# Ethernet.net
KiCad netlist of a schematic drawn in Altium Designer
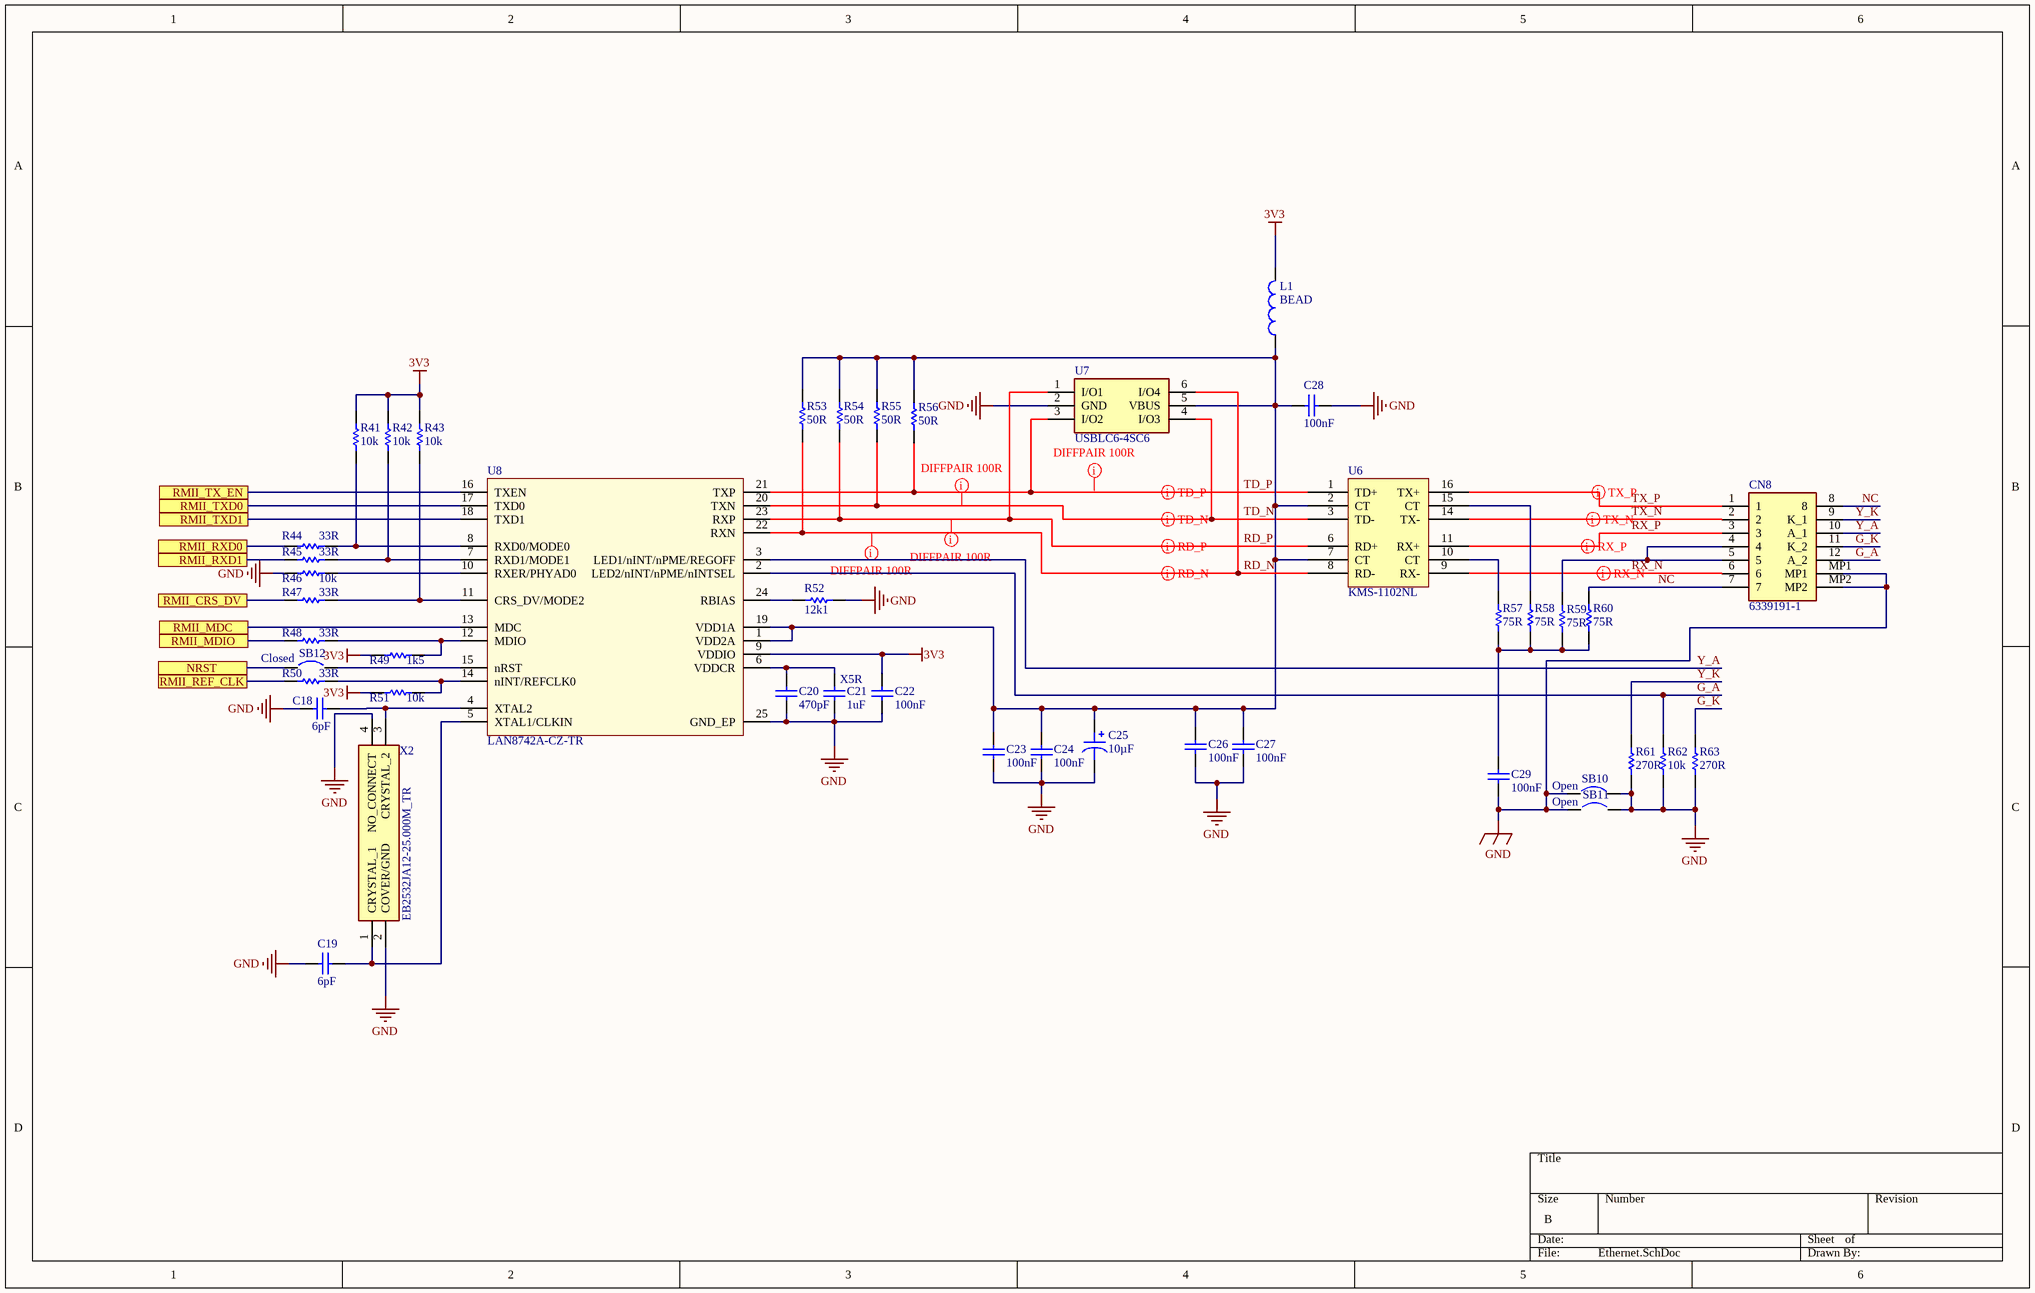
[diagram p0: Ethernet.SchDoc]

(export (version "E")
  (design (tool "Eeschema 10.0.6"))
  (components
    (comp (ref "C18")
      (value "6pF")
      (footprint "1608[0603]")
      (description "Capacitor")
      (fields (field (name "Comment") "Cap") (field (name "PUBLISHER") "Altium Limited"))
      (libsource (lib "Miscellaneous Devices") (part "Cap"))
    )
    (comp (ref "C19")
      (value "6pF")
      (footprint "1608[0603]")
      (description "Capacitor")
      (fields (field (name "Comment") "Cap") (field (name "PUBLISHER") "Altium Limited"))
      (libsource (lib "Miscellaneous Devices") (part "Cap"))
    )
    (comp (ref "C20")
      (value "470pF")
      (footprint "1608[0603]")
      (description "Capacitor")
      (fields (field (name "Comment") "Cap") (field (name "PUBLISHER") "Altium Limited"))
      (libsource (lib "Miscellaneous Devices") (part "Cap"))
    )
    (comp (ref "C21")
      (value "X5R")
      (footprint "1608[0603]")
      (description "Capacitor")
      (fields (field (name "ALTIUM_VALUE") "1uF") (field (name "PUBLISHER") "Altium Limited"))
      (libsource (lib "Miscellaneous Devices") (part "Cap"))
    )
    (comp (ref "C22")
      (value "100nF")
      (footprint "1608[0603]")
      (description "Capacitor")
      (fields (field (name "Comment") "Cap") (field (name "PUBLISHER") "Altium Limited"))
      (libsource (lib "Miscellaneous Devices") (part "Cap"))
    )
    (comp (ref "C23")
      (value "100nF")
      (footprint "1608[0603]")
      (description "Capacitor")
      (fields (field (name "Comment") "Cap") (field (name "PUBLISHER") "Altium Limited"))
      (libsource (lib "Miscellaneous Devices") (part "Cap"))
    )
    (comp (ref "C24")
      (value "100nF")
      (footprint "1608[0603]")
      (description "Capacitor")
      (fields (field (name "Comment") "Cap") (field (name "PUBLISHER") "Altium Limited"))
      (libsource (lib "Miscellaneous Devices") (part "Cap"))
    )
    (comp (ref "C25")
      (value "10µF")
      (footprint "CAP ALSMD 5.3MM H5.4MM")
      (description "CAP ALUM 10UF 20% 16V SMD")
      (fields (field (name "PART NUMBER") "UZP1C100MCL1GB") (field (name "MANUFACTURER") "Nichicon"))
      (libsource (lib "Celestial Altium Library - altium_library") (part "Polarised Capacitor"))
    )
    (comp (ref "C26")
      (value "100nF")
      (footprint "1608[0603]")
      (description "Capacitor")
      (fields (field (name "Comment") "Cap") (field (name "PUBLISHER") "Altium Limited"))
      (libsource (lib "Miscellaneous Devices") (part "Cap"))
    )
    (comp (ref "C27")
      (value "100nF")
      (footprint "1608[0603]")
      (description "Capacitor")
      (fields (field (name "Comment") "Cap") (field (name "PUBLISHER") "Altium Limited"))
      (libsource (lib "Miscellaneous Devices") (part "Cap"))
    )
    (comp (ref "C28")
      (value "100nF")
      (footprint "1608[0603]")
      (description "Capacitor")
      (fields (field (name "Comment") "Cap") (field (name "PUBLISHER") "Altium Limited"))
      (libsource (lib "Miscellaneous Devices") (part "Cap"))
    )
    (comp (ref "C29")
      (value "100nF")
      (footprint "1608[0603]")
      (description "Capacitor")
      (fields (field (name "Comment") "Cap") (field (name "PUBLISHER") "Altium Limited"))
      (libsource (lib "Miscellaneous Devices") (part "Cap"))
    )
    (comp (ref "CN8")
      (value "6339191-1")
      (footprint "SamacSys:63391911")
      (description "Connector")
      (fields (field (name "MOUSER PART NUMBER") "571-6339191-1"))
      (libsource (lib "*") (part "6339191-1"))
    )
    (comp (ref "L1")
      (value "BEAD")
      (footprint "0603L")
      (description "Inductor")
      (fields (field (name "PUBLISHER") "Altium Limited"))
      (libsource (lib "MB1137") (part "Inductor"))
    )
    (comp (ref "R41")
      (value "10k")
      (footprint "1608[0603]")
      (description "Resistor")
      (fields (field (name "Comment") "Res1") (field (name "PUBLISHER") "Altium Limited"))
      (libsource (lib "Miscellaneous Devices") (part "Res1"))
    )
    (comp (ref "R42")
      (value "10k")
      (footprint "1608[0603]")
      (description "Resistor")
      (fields (field (name "Comment") "Res1") (field (name "PUBLISHER") "Altium Limited"))
      (libsource (lib "Miscellaneous Devices") (part "Res1"))
    )
    (comp (ref "R43")
      (value "10k")
      (footprint "1608[0603]")
      (description "Resistor")
      (fields (field (name "Comment") "Res1") (field (name "PUBLISHER") "Altium Limited"))
      (libsource (lib "Miscellaneous Devices") (part "Res1"))
    )
    (comp (ref "R44")
      (value "33R")
      (footprint "1608[0603]")
      (description "Resistor")
      (fields (field (name "Comment") "Res1") (field (name "PUBLISHER") "Altium Limited"))
      (libsource (lib "Miscellaneous Devices") (part "Res1"))
    )
    (comp (ref "R45")
      (value "33R")
      (footprint "1608[0603]")
      (description "Resistor")
      (fields (field (name "Comment") "Res1") (field (name "PUBLISHER") "Altium Limited"))
      (libsource (lib "Miscellaneous Devices") (part "Res1"))
    )
    (comp (ref "R46")
      (value "10k")
      (footprint "1608[0603]")
      (description "Resistor")
      (fields (field (name "Comment") "Res1") (field (name "PUBLISHER") "Altium Limited"))
      (libsource (lib "Miscellaneous Devices") (part "Res1"))
    )
    (comp (ref "R47")
      (value "33R")
      (footprint "1608[0603]")
      (description "Resistor")
      (fields (field (name "Comment") "Res1") (field (name "PUBLISHER") "Altium Limited"))
      (libsource (lib "Miscellaneous Devices") (part "Res1"))
    )
    (comp (ref "R48")
      (value "33R")
      (footprint "1608[0603]")
      (description "Resistor")
      (fields (field (name "Comment") "Res1") (field (name "PUBLISHER") "Altium Limited"))
      (libsource (lib "Miscellaneous Devices") (part "Res1"))
    )
    (comp (ref "R49")
      (value "1k5")
      (footprint "1608[0603]")
      (description "Resistor")
      (fields (field (name "Comment") "Res1") (field (name "PUBLISHER") "Altium Limited"))
      (libsource (lib "Miscellaneous Devices") (part "Res1"))
    )
    (comp (ref "R50")
      (value "33R")
      (footprint "1608[0603]")
      (description "Resistor")
      (fields (field (name "Comment") "Res1") (field (name "PUBLISHER") "Altium Limited"))
      (libsource (lib "Miscellaneous Devices") (part "Res1"))
    )
    (comp (ref "R51")
      (value "10k")
      (footprint "1608[0603]")
      (description "Resistor")
      (fields (field (name "Comment") "Res1") (field (name "PUBLISHER") "Altium Limited"))
      (libsource (lib "Miscellaneous Devices") (part "Res1"))
    )
    (comp (ref "R52")
      (value "12k1")
      (footprint "1608[0603]")
      (description "Resistor")
      (fields (field (name "Comment") "Res1") (field (name "PUBLISHER") "Altium Limited"))
      (libsource (lib "Miscellaneous Devices") (part "Res1"))
    )
    (comp (ref "R53")
      (value "50R")
      (footprint "1608[0603]")
      (description "Resistor")
      (fields (field (name "Comment") "Res1") (field (name "PUBLISHER") "Altium Limited"))
      (libsource (lib "Miscellaneous Devices") (part "Res1"))
    )
    (comp (ref "R54")
      (value "50R")
      (footprint "1608[0603]")
      (description "Resistor")
      (fields (field (name "Comment") "Res1") (field (name "PUBLISHER") "Altium Limited"))
      (libsource (lib "Miscellaneous Devices") (part "Res1"))
    )
    (comp (ref "R55")
      (value "50R")
      (footprint "1608[0603]")
      (description "Resistor")
      (fields (field (name "Comment") "Res1") (field (name "PUBLISHER") "Altium Limited"))
      (libsource (lib "Miscellaneous Devices") (part "Res1"))
    )
    (comp (ref "R56")
      (value "50R")
      (footprint "1608[0603]")
      (description "Resistor")
      (fields (field (name "Comment") "Res1") (field (name "PUBLISHER") "Altium Limited"))
      (libsource (lib "Miscellaneous Devices") (part "Res1"))
    )
    (comp (ref "R57")
      (value "75R")
      (footprint "1608[0603]")
      (description "Resistor")
      (fields (field (name "Comment") "Res1") (field (name "PUBLISHER") "Altium Limited"))
      (libsource (lib "Miscellaneous Devices") (part "Res1"))
    )
    (comp (ref "R58")
      (value "75R")
      (footprint "1608[0603]")
      (description "Resistor")
      (fields (field (name "Comment") "Res1") (field (name "PUBLISHER") "Altium Limited"))
      (libsource (lib "Miscellaneous Devices") (part "Res1"))
    )
    (comp (ref "R59")
      (value "75R")
      (footprint "1608[0603]")
      (description "Resistor")
      (fields (field (name "Comment") "Res1") (field (name "PUBLISHER") "Altium Limited"))
      (libsource (lib "Miscellaneous Devices") (part "Res1"))
    )
    (comp (ref "R60")
      (value "75R")
      (footprint "1608[0603]")
      (description "Resistor")
      (fields (field (name "Comment") "Res1") (field (name "PUBLISHER") "Altium Limited"))
      (libsource (lib "Miscellaneous Devices") (part "Res1"))
    )
    (comp (ref "R61")
      (value "270R")
      (footprint "1608[0603]")
      (description "Resistor")
      (fields (field (name "Comment") "Res1") (field (name "PUBLISHER") "Altium Limited"))
      (libsource (lib "Miscellaneous Devices") (part "Res1"))
    )
    (comp (ref "R62")
      (value "10k")
      (footprint "1608[0603]")
      (description "Resistor")
      (fields (field (name "Comment") "Res1") (field (name "PUBLISHER") "Altium Limited"))
      (libsource (lib "Miscellaneous Devices") (part "Res1"))
    )
    (comp (ref "R63")
      (value "270R")
      (footprint "1608[0603]")
      (description "Resistor")
      (fields (field (name "Comment") "Res1") (field (name "PUBLISHER") "Altium Limited"))
      (libsource (lib "Miscellaneous Devices") (part "Res1"))
    )
    (comp (ref "SB10")
      (value "Open")
      (footprint "SB_0603")
      (description "Circuit Breaker")
      (fields (field (name "PUBLISHER") "Altium Limited"))
      (libsource (lib "MB1137") (part "Circuit Breaker"))
    )
    (comp (ref "SB11")
      (value "Open")
      (footprint "SB_0603")
      (description "Circuit Breaker")
      (fields (field (name "PUBLISHER") "Altium Limited"))
      (libsource (lib "MB1137") (part "Circuit Breaker"))
    )
    (comp (ref "SB12")
      (value "Closed")
      (footprint "SB_0603")
      (description "Circuit Breaker")
      (fields (field (name "PUBLISHER") "Altium Limited"))
      (libsource (lib "MB1137") (part "Circuit Breaker"))
    )
    (comp (ref "U6")
      (value "KMS-1102NL")
      (footprint "Transformer")
      (libsource (lib "MB1137") (part "KMS-1102NL"))
    )
    (comp (ref "U7")
      (value "USBLC6-4SC6")
      (footprint "SamacSys:SOT95P280X145-6N")
      (description "Integrated Circuit")
      (fields (field (name "MOUSER PART NUMBER") "511-USBLC6-4SC6"))
      (libsource (lib "*") (part "USBLC6-4SC6"))
    )
    (comp (ref "U8")
      (value "LAN8742A-CZ-TR")
      (footprint "QFN24_0R5_4X4")
      (libsource (lib "MB1137") (part "LAN8742A-CZ-TR"))
    )
    (comp (ref "X2")
      (value "EB2532JA12-25.000M_TR")
      (footprint "SamacSys:EB2532JA1225000MTR")
      (description "Crystal or Oscillator")
      (fields
        (field (name "MANUFACTURER_PART_NUMBER") "EB2532JA12-25.000M TR")
        (field (name "MOUSER PART NUMBER") "669-EB2532JA12-25T")
      )
      (libsource (lib "*") (part "EB2532JA12-25.000M_TR"))
    )
  )
  (nets
    (net (code "1") (name "/G_A") (class "Default")
      (node (ref "CN8") (pin "12") (pinfunction "A_2_12") (pintype "passive"))
      (node (ref "R62") (pin "2") (pinfunction "2_2") (pintype "passive"))
      (node (ref "U8") (pin "2") (pinfunction "LED2/nINT/nPME/nINTSEL_2") (pintype "passive"))
    )
    (net (code "2") (name "/G_K") (class "Default")
      (node (ref "CN8") (pin "11") (pinfunction "K_2_11") (pintype "passive"))
      (node (ref "R63") (pin "2") (pinfunction "2_2") (pintype "passive"))
    )
    (net (code "3") (name "/NC") (class "Default")
      (node (ref "CN8") (pin "7") (pinfunction "7_7") (pintype "passive"))
      (node (ref "CN8") (pin "8") (pinfunction "8_8") (pintype "passive"))
      (node (ref "R60") (pin "2") (pinfunction "2_2") (pintype "passive"))
    )
    (net (code "4") (name "/NRST") (class "Default")
      (node (ref "SB12") (pin "1") (pinfunction "1_1") (pintype "passive"))
    )
    (net (code "5") (name "/RD_N") (class "Default")
      (node (ref "R53") (pin "1") (pinfunction "1_1") (pintype "passive"))
      (node (ref "U6") (pin "8") (pinfunction "RD-_8") (pintype "passive"))
      (node (ref "U7") (pin "6") (pinfunction "I/O4_6") (pintype "passive"))
      (node (ref "U8") (pin "22") (pinfunction "RXN_22") (pintype "passive"))
    )
    (net (code "6") (name "/RD_P") (class "Default")
      (node (ref "R54") (pin "1") (pinfunction "1_1") (pintype "passive"))
      (node (ref "U6") (pin "6") (pinfunction "RD+_6") (pintype "passive"))
      (node (ref "U7") (pin "1") (pinfunction "I/O1_1") (pintype "passive"))
      (node (ref "U8") (pin "23") (pinfunction "RXP_23") (pintype "passive"))
    )
    (net (code "7") (name "/RMII_CRS_DV") (class "Default")
      (node (ref "R47") (pin "2") (pinfunction "2_2") (pintype "passive"))
    )
    (net (code "8") (name "/RMII_MDC") (class "Default")
      (node (ref "U8") (pin "13") (pinfunction "MDC_13") (pintype "passive"))
    )
    (net (code "9") (name "/RMII_MDIO") (class "Default")
      (node (ref "R48") (pin "2") (pinfunction "2_2") (pintype "passive"))
    )
    (net (code "10") (name "/RMII_REF_CLK") (class "Default")
      (node (ref "R50") (pin "2") (pinfunction "2_2") (pintype "passive"))
    )
    (net (code "11") (name "/RMII_RXD0") (class "Default")
      (node (ref "R44") (pin "2") (pinfunction "2_2") (pintype "passive"))
    )
    (net (code "12") (name "/RMII_RXD1") (class "Default")
      (node (ref "R45") (pin "2") (pinfunction "2_2") (pintype "passive"))
    )
    (net (code "13") (name "/RMII_TXD0") (class "Default")
      (node (ref "U8") (pin "17") (pinfunction "TXD0_17") (pintype "passive"))
    )
    (net (code "14") (name "/RMII_TXD1") (class "Default")
      (node (ref "U8") (pin "18") (pinfunction "TXD1_18") (pintype "passive"))
    )
    (net (code "15") (name "/RMII_TX_EN") (class "Default")
      (node (ref "U8") (pin "16") (pinfunction "TXEN_16") (pintype "passive"))
    )
    (net (code "16") (name "/RX_N") (class "Default")
      (node (ref "CN8") (pin "6") (pinfunction "6_6") (pintype "passive"))
      (node (ref "U6") (pin "9") (pinfunction "RX-_9") (pintype "passive"))
    )
    (net (code "17") (name "/RX_P") (class "Default")
      (node (ref "CN8") (pin "3") (pinfunction "3_3") (pintype "passive"))
      (node (ref "U6") (pin "11") (pinfunction "RX+_11") (pintype "passive"))
    )
    (net (code "18") (name "/TD_N") (class "Default")
      (node (ref "R55") (pin "1") (pinfunction "1_1") (pintype "passive"))
      (node (ref "U6") (pin "3") (pinfunction "TD-_3") (pintype "passive"))
      (node (ref "U7") (pin "4") (pinfunction "I/O3_4") (pintype "passive"))
      (node (ref "U8") (pin "20") (pinfunction "TXN_20") (pintype "passive"))
    )
    (net (code "19") (name "/TD_P") (class "Default")
      (node (ref "R56") (pin "1") (pinfunction "1_1") (pintype "passive"))
      (node (ref "U6") (pin "1") (pinfunction "TD+_1") (pintype "passive"))
      (node (ref "U7") (pin "3") (pinfunction "I/O2_3") (pintype "passive"))
      (node (ref "U8") (pin "21") (pinfunction "TXP_21") (pintype "passive"))
    )
    (net (code "20") (name "/TX_N") (class "Default")
      (node (ref "CN8") (pin "2") (pinfunction "2_2") (pintype "passive"))
      (node (ref "U6") (pin "14") (pinfunction "TX-_14") (pintype "passive"))
    )
    (net (code "21") (name "/TX_P") (class "Default")
      (node (ref "CN8") (pin "1") (pinfunction "1_1") (pintype "passive"))
      (node (ref "U6") (pin "16") (pinfunction "TX+_16") (pintype "passive"))
    )
    (net (code "22") (name "/Y_A") (class "Default")
      (node (ref "CN8") (pin "10") (pinfunction "A_1_10") (pintype "passive"))
      (node (ref "U8") (pin "3") (pinfunction "LED1/nINT/nPME/REGOFF_3") (pintype "passive"))
    )
    (net (code "23") (name "/Y_K") (class "Default")
      (node (ref "CN8") (pin "9") (pinfunction "K_1_9") (pintype "passive"))
      (node (ref "R61") (pin "2") (pinfunction "2_2") (pintype "passive"))
    )
    (net (code "24") (name "3V3") (class "Default")
      (node (ref "C22") (pin "1") (pinfunction "1_1") (pintype "passive"))
      (node (ref "L1") (pin "2") (pinfunction "2_2") (pintype "passive"))
      (node (ref "R41") (pin "2") (pinfunction "2_2") (pintype "passive"))
      (node (ref "R42") (pin "2") (pinfunction "2_2") (pintype "passive"))
      (node (ref "R43") (pin "2") (pinfunction "2_2") (pintype "passive"))
      (node (ref "R49") (pin "2") (pinfunction "2_2") (pintype "passive"))
      (node (ref "R51") (pin "2") (pinfunction "2_2") (pintype "passive"))
      (node (ref "U8") (pin "9") (pinfunction "VDDIO_9") (pintype "passive"))
    )
    (net (code "25") (name "GND") (class "Default")
      (node (ref "C18") (pin "1") (pinfunction "1_1") (pintype "passive"))
      (node (ref "C19") (pin "1") (pinfunction "1_1") (pintype "passive"))
      (node (ref "C20") (pin "2") (pinfunction "2_2") (pintype "passive"))
      (node (ref "C21") (pin "2") (pinfunction "2_2") (pintype "passive"))
      (node (ref "C22") (pin "2") (pinfunction "2_2") (pintype "passive"))
      (node (ref "C23") (pin "2") (pinfunction "2_2") (pintype "passive"))
      (node (ref "C24") (pin "2") (pinfunction "2_2") (pintype "passive"))
      (node (ref "C25") (pin "2") (pinfunction "2_2") (pintype "passive"))
      (node (ref "C26") (pin "2") (pinfunction "2_2") (pintype "passive"))
      (node (ref "C27") (pin "2") (pinfunction "2_2") (pintype "passive"))
      (node (ref "C28") (pin "1") (pinfunction "1_1") (pintype "passive"))
      (node (ref "C29") (pin "1") (pinfunction "1_1") (pintype "passive"))
      (node (ref "CN8") (pin "MP1") (pinfunction "MP1_MP1") (pintype "passive"))
      (node (ref "CN8") (pin "MP2") (pinfunction "MP2_MP2") (pintype "passive"))
      (node (ref "R46") (pin "2") (pinfunction "2_2") (pintype "passive"))
      (node (ref "R52") (pin "1") (pinfunction "1_1") (pintype "passive"))
      (node (ref "R61") (pin "1") (pinfunction "1_1") (pintype "passive"))
      (node (ref "R62") (pin "1") (pinfunction "1_1") (pintype "passive"))
      (node (ref "R63") (pin "1") (pinfunction "1_1") (pintype "passive"))
      (node (ref "SB10") (pin "1") (pinfunction "1_1") (pintype "passive"))
      (node (ref "SB10") (pin "2") (pinfunction "2_2") (pintype "passive"))
      (node (ref "SB11") (pin "1") (pinfunction "1_1") (pintype "passive"))
      (node (ref "SB11") (pin "2") (pinfunction "2_2") (pintype "passive"))
      (node (ref "U7") (pin "2") (pinfunction "GND_2") (pintype "passive"))
      (node (ref "U8") (pin "25") (pinfunction "GND_EP_25") (pintype "passive"))
      (node (ref "X2") (pin "2") (pinfunction "COVER/GND_2") (pintype "passive"))
      (node (ref "X2") (pin "4") (pinfunction "NO_CONNECT_4") (pintype "passive"))
    )
    (net (code "26") (name "Net-(C29-Pad2)") (class "Default")
      (node (ref "C29") (pin "2") (pinfunction "2_2") (pintype "passive"))
      (node (ref "R57") (pin "1") (pinfunction "1_1") (pintype "passive"))
      (node (ref "R58") (pin "1") (pinfunction "1_1") (pintype "passive"))
      (node (ref "R59") (pin "1") (pinfunction "1_1") (pintype "passive"))
      (node (ref "R60") (pin "1") (pinfunction "1_1") (pintype "passive"))
    )
    (net (code "27") (name "Net-(CN8-Pad4)") (class "Default")
      (node (ref "CN8") (pin "4") (pinfunction "4_4") (pintype "passive"))
      (node (ref "CN8") (pin "5") (pinfunction "5_5") (pintype "passive"))
      (node (ref "R59") (pin "2") (pinfunction "2_2") (pintype "passive"))
    )
    (net (code "28") (name "Net-(R57-Pad2)") (class "Default")
      (node (ref "R57") (pin "2") (pinfunction "2_2") (pintype "passive"))
      (node (ref "U6") (pin "10") (pinfunction "CT_10") (pintype "passive"))
    )
    (net (code "29") (name "Net-(R58-Pad2)") (class "Default")
      (node (ref "R58") (pin "2") (pinfunction "2_2") (pintype "passive"))
      (node (ref "U6") (pin "15") (pinfunction "CT_15") (pintype "passive"))
    )
    (net (code "30") (name "Net-(U7-VBUS)") (class "Default")
      (node (ref "C23") (pin "1") (pinfunction "1_1") (pintype "passive"))
      (node (ref "C24") (pin "1") (pinfunction "1_1") (pintype "passive"))
      (node (ref "C25") (pin "1") (pinfunction "1_1") (pintype "passive"))
      (node (ref "C26") (pin "1") (pinfunction "1_1") (pintype "passive"))
      (node (ref "C27") (pin "1") (pinfunction "1_1") (pintype "passive"))
      (node (ref "C28") (pin "2") (pinfunction "2_2") (pintype "passive"))
      (node (ref "L1") (pin "1") (pinfunction "1_1") (pintype "passive"))
      (node (ref "R53") (pin "2") (pinfunction "2_2") (pintype "passive"))
      (node (ref "R54") (pin "2") (pinfunction "2_2") (pintype "passive"))
      (node (ref "R55") (pin "2") (pinfunction "2_2") (pintype "passive"))
      (node (ref "R56") (pin "2") (pinfunction "2_2") (pintype "passive"))
      (node (ref "U6") (pin "2") (pinfunction "CT_2") (pintype "passive"))
      (node (ref "U6") (pin "7") (pinfunction "CT_7") (pintype "passive"))
      (node (ref "U7") (pin "5") (pinfunction "VBUS_5") (pintype "passive"))
      (node (ref "U8") (pin "1") (pinfunction "VDD2A_1") (pintype "passive"))
      (node (ref "U8") (pin "19") (pinfunction "VDD1A_19") (pintype "passive"))
    )
    (net (code "31") (name "Net-(U8-CRS_DV{slash}MODE2)") (class "Default")
      (node (ref "R43") (pin "1") (pinfunction "1_1") (pintype "passive"))
      (node (ref "R47") (pin "1") (pinfunction "1_1") (pintype "passive"))
      (node (ref "U8") (pin "11") (pinfunction "CRS_DV/MODE2_11") (pintype "passive"))
    )
    (net (code "32") (name "Net-(U8-MDIO)") (class "Default")
      (node (ref "R48") (pin "1") (pinfunction "1_1") (pintype "passive"))
      (node (ref "R49") (pin "1") (pinfunction "1_1") (pintype "passive"))
      (node (ref "U8") (pin "12") (pinfunction "MDIO_12") (pintype "passive"))
    )
    (net (code "33") (name "Net-(U8-RBIAS)") (class "Default")
      (node (ref "R52") (pin "2") (pinfunction "2_2") (pintype "passive"))
      (node (ref "U8") (pin "24") (pinfunction "RBIAS_24") (pintype "passive"))
    )
    (net (code "34") (name "Net-(U8-RXD0{slash}MODE0)") (class "Default")
      (node (ref "R41") (pin "1") (pinfunction "1_1") (pintype "passive"))
      (node (ref "R44") (pin "1") (pinfunction "1_1") (pintype "passive"))
      (node (ref "U8") (pin "8") (pinfunction "RXD0/MODE0_8") (pintype "passive"))
    )
    (net (code "35") (name "Net-(U8-RXD1{slash}MODE1)") (class "Default")
      (node (ref "R42") (pin "1") (pinfunction "1_1") (pintype "passive"))
      (node (ref "R45") (pin "1") (pinfunction "1_1") (pintype "passive"))
      (node (ref "U8") (pin "7") (pinfunction "RXD1/MODE1_7") (pintype "passive"))
    )
    (net (code "36") (name "Net-(U8-RXER{slash}PHYAD0)") (class "Default")
      (node (ref "R46") (pin "1") (pinfunction "1_1") (pintype "passive"))
      (node (ref "U8") (pin "10") (pinfunction "RXER/PHYAD0_10") (pintype "passive"))
    )
    (net (code "37") (name "Net-(U8-VDDCR)") (class "Default")
      (node (ref "C20") (pin "1") (pinfunction "1_1") (pintype "passive"))
      (node (ref "C21") (pin "1") (pinfunction "1_1") (pintype "passive"))
      (node (ref "U8") (pin "6") (pinfunction "VDDCR_6") (pintype "passive"))
    )
    (net (code "38") (name "Net-(U8-XTAL1{slash}CLKIN)") (class "Default")
      (node (ref "C19") (pin "2") (pinfunction "2_2") (pintype "passive"))
      (node (ref "U8") (pin "5") (pinfunction "XTAL1/CLKIN_5") (pintype "passive"))
      (node (ref "X2") (pin "1") (pinfunction "CRYSTAL_1_1") (pintype "passive"))
    )
    (net (code "39") (name "Net-(U8-XTAL2)") (class "Default")
      (node (ref "C18") (pin "2") (pinfunction "2_2") (pintype "passive"))
      (node (ref "U8") (pin "4") (pinfunction "XTAL2_4") (pintype "passive"))
      (node (ref "X2") (pin "3") (pinfunction "CRYSTAL_2_3") (pintype "passive"))
    )
    (net (code "40") (name "Net-(U8-nINT{slash}REFCLK0)") (class "Default")
      (node (ref "R50") (pin "1") (pinfunction "1_1") (pintype "passive"))
      (node (ref "R51") (pin "1") (pinfunction "1_1") (pintype "passive"))
      (node (ref "U8") (pin "14") (pinfunction "nINT/REFCLK0_14") (pintype "passive"))
    )
    (net (code "41") (name "Net-(U8-nRST)") (class "Default")
      (node (ref "SB12") (pin "2") (pinfunction "2_2") (pintype "passive"))
      (node (ref "U8") (pin "15") (pinfunction "nRST_15") (pintype "passive"))
    )
  )
)
